# dubber.net
KiCad netlist of a schematic drawn in EAGLE
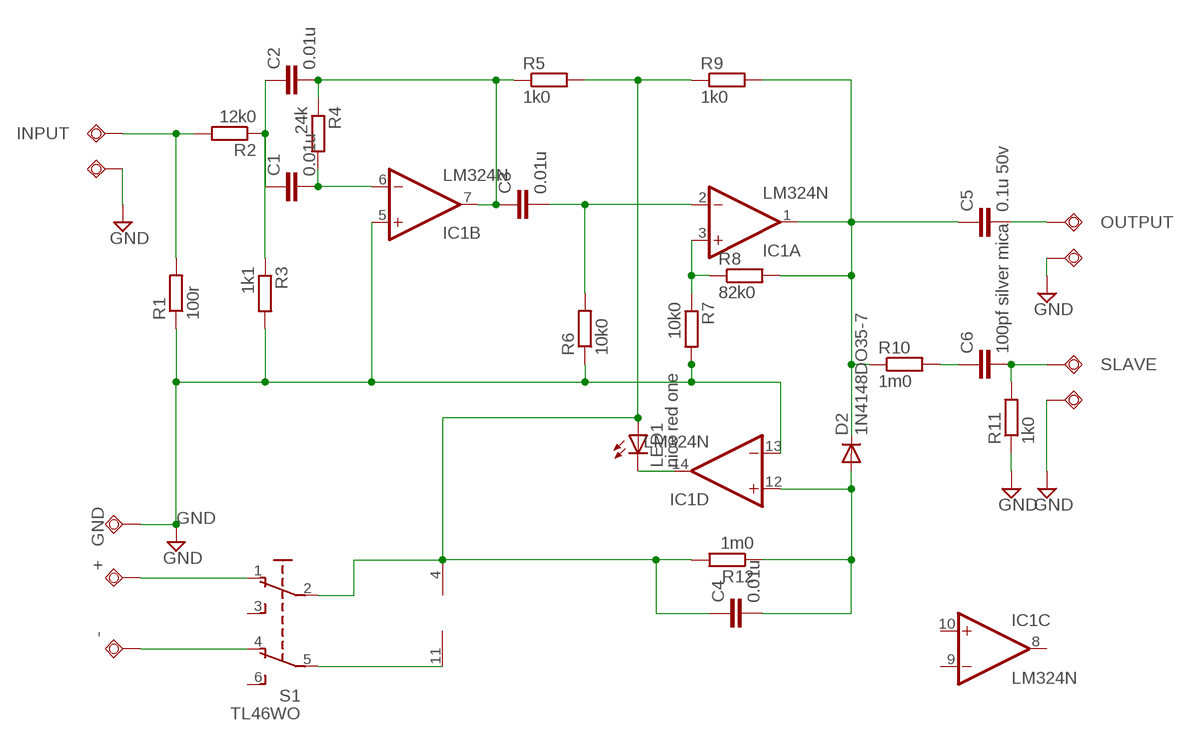
[diagram p0: schematic, sheet 1]

(export (version "E")
  (design (tool "Eeschema 10.0.6"))
  (components
    (comp (ref "+")
      (value "TPSQPAD1-13Y")
      (footprint "eagle-import:P1-13Y")
      (libsource (lib "eagle-import") (part "TPSQPAD1-13Y"))
    )
    (comp (ref "-")
      (value "TPSQPAD1-13Y")
      (footprint "eagle-import:P1-13Y")
      (libsource (lib "eagle-import") (part "TPSQPAD1-13Y"))
    )
    (comp (ref "C1")
      (value "0.01u")
      (footprint "eagle-import:C025-025X050")
      (libsource (lib "eagle-import") (part "C-EU025-025X050"))
    )
    (comp (ref "C2")
      (value "0.01u")
      (footprint "eagle-import:C025-025X050")
      (libsource (lib "eagle-import") (part "C-EU025-025X050"))
    )
    (comp (ref "C3")
      (value "0.01u")
      (footprint "eagle-import:C025-025X050")
      (libsource (lib "eagle-import") (part "C-EU025-025X050"))
    )
    (comp (ref "C4")
      (value "0.01u")
      (footprint "eagle-import:C025-025X050")
      (libsource (lib "eagle-import") (part "C-EU025-025X050"))
    )
    (comp (ref "C5")
      (value "0.1u 50v")
      (footprint "eagle-import:C025-025X050")
      (libsource (lib "eagle-import") (part "C-EU025-025X050"))
    )
    (comp (ref "C6")
      (value "100pf silver mica")
      (footprint "eagle-import:C025-025X050")
      (libsource (lib "eagle-import") (part "C-EU025-025X050"))
    )
    (comp (ref "D2")
      (value "1N4148DO35-7")
      (footprint "eagle-import:DO35-7")
      (libsource (lib "eagle-import") (part "1N4148DO35-7"))
    )
    (comp (ref "GND")
      (value "TPSQPAD1-13Y")
      (footprint "eagle-import:P1-13Y")
      (libsource (lib "eagle-import") (part "TPSQPAD1-13Y"))
    )
    (comp (ref "IC1")
      (value "LM324N")
      (footprint "eagle-import:DIL14")
      (libsource (lib "eagle-import") (part "LM324N"))
    )
    (comp (ref "INPUT")
      (value "TPSQPAD1-13Y")
      (footprint "eagle-import:P1-13Y")
      (libsource (lib "eagle-import") (part "TPSQPAD1-13Y"))
    )
    (comp (ref "LED1")
      (value "nice red one")
      (footprint "eagle-import:LED5MM")
      (libsource (lib "eagle-import") (part "LED5MM"))
    )
    (comp (ref "OUTPUT")
      (value "TPSQPAD1-13Y")
      (footprint "eagle-import:P1-13Y")
      (libsource (lib "eagle-import") (part "TPSQPAD1-13Y"))
    )
    (comp (ref "P1-G")
      (value "TPSQPAD1-13Y")
      (footprint "eagle-import:P1-13Y")
      (libsource (lib "eagle-import") (part "TPSQPAD1-13Y"))
    )
    (comp (ref "P2-G")
      (value "TPSQPAD1-13Y")
      (footprint "eagle-import:P1-13Y")
      (libsource (lib "eagle-import") (part "TPSQPAD1-13Y"))
    )
    (comp (ref "P3-G")
      (value "TPSQPAD1-13Y")
      (footprint "eagle-import:P1-13Y")
      (libsource (lib "eagle-import") (part "TPSQPAD1-13Y"))
    )
    (comp (ref "R1")
      (value "100r")
      (footprint "eagle-import:0207_10")
      (libsource (lib "eagle-import") (part "R-EU_0207/10"))
    )
    (comp (ref "R2")
      (value "12k0")
      (footprint "eagle-import:0207_10")
      (libsource (lib "eagle-import") (part "R-EU_0207/10"))
    )
    (comp (ref "R3")
      (value "1k1")
      (footprint "eagle-import:0207_10")
      (libsource (lib "eagle-import") (part "R-EU_0207/10"))
    )
    (comp (ref "R4")
      (value "24k")
      (footprint "eagle-import:0207_10")
      (libsource (lib "eagle-import") (part "R-EU_0207/10"))
    )
    (comp (ref "R5")
      (value "1k0")
      (footprint "eagle-import:0207_10")
      (libsource (lib "eagle-import") (part "R-EU_0207/10"))
    )
    (comp (ref "R6")
      (value "10k0")
      (footprint "eagle-import:0207_10")
      (libsource (lib "eagle-import") (part "R-EU_0207/10"))
    )
    (comp (ref "R7")
      (value "10k0")
      (footprint "eagle-import:0207_10")
      (libsource (lib "eagle-import") (part "R-EU_0207/10"))
    )
    (comp (ref "R8")
      (value "82k0")
      (footprint "eagle-import:0207_10")
      (libsource (lib "eagle-import") (part "R-EU_0207/10"))
    )
    (comp (ref "R9")
      (value "1k0")
      (footprint "eagle-import:0207_10")
      (libsource (lib "eagle-import") (part "R-EU_0207/10"))
    )
    (comp (ref "R10")
      (value "1m0")
      (footprint "eagle-import:0207_10")
      (libsource (lib "eagle-import") (part "R-EU_0207/10"))
    )
    (comp (ref "R11")
      (value "1k0")
      (footprint "eagle-import:0207_10")
      (libsource (lib "eagle-import") (part "R-EU_0207/10"))
    )
    (comp (ref "R12")
      (value "1m0")
      (footprint "eagle-import:0207_10")
      (libsource (lib "eagle-import") (part "R-EU_0207/10"))
    )
    (comp (ref "S1")
      (value "TL46WO")
      (footprint "eagle-import:TL4XWO")
      (libsource (lib "eagle-import") (part "TL46WO"))
    )
    (comp (ref "SLAVE")
      (value "TPSQPAD1-13Y")
      (footprint "eagle-import:P1-13Y")
      (libsource (lib "eagle-import") (part "TPSQPAD1-13Y"))
    )
  )
  (nets
    (net (code "1") (name "GND") (class "Default")
      (node (ref "GND") (pin "TP") (pinfunction "TP_TP") (pintype "input"))
      (node (ref "IC1") (pin "13") (pinfunction "-IN_13") (pintype "input"))
      (node (ref "IC1") (pin "5") (pinfunction "+IN_5") (pintype "input"))
      (node (ref "P1-G") (pin "TP") (pinfunction "TP_TP") (pintype "input"))
      (node (ref "P2-G") (pin "TP") (pinfunction "TP_TP") (pintype "input"))
      (node (ref "P3-G") (pin "TP") (pinfunction "TP_TP") (pintype "input"))
      (node (ref "R1") (pin "1") (pinfunction "1_1") (pintype "passive"))
      (node (ref "R11") (pin "1") (pinfunction "1_1") (pintype "passive"))
      (node (ref "R3") (pin "2") (pinfunction "2_2") (pintype "passive"))
      (node (ref "R6") (pin "1") (pinfunction "1_1") (pintype "passive"))
      (node (ref "R7") (pin "2") (pinfunction "2_2") (pintype "passive"))
    )
    (net (code "2") (name "Net-(C1-Pad1)") (class "Default")
      (node (ref "C1") (pin "1") (pinfunction "1_1") (pintype "passive"))
      (node (ref "C2") (pin "1") (pinfunction "1_1") (pintype "passive"))
      (node (ref "R2") (pin "1") (pinfunction "1_1") (pintype "passive"))
      (node (ref "R3") (pin "1") (pinfunction "1_1") (pintype "passive"))
    )
    (net (code "3") (name "Net-(C5-Pad2)") (class "Default")
      (node (ref "C5") (pin "2") (pinfunction "2_2") (pintype "passive"))
      (node (ref "OUTPUT") (pin "TP") (pinfunction "TP_TP") (pintype "input"))
    )
    (net (code "4") (name "Net-(C6-Pad1)") (class "Default")
      (node (ref "C6") (pin "1") (pinfunction "1_1") (pintype "passive"))
      (node (ref "R10") (pin "2") (pinfunction "2_2") (pintype "passive"))
    )
    (net (code "5") (name "Net-(C6-Pad2)") (class "Default")
      (node (ref "C6") (pin "2") (pinfunction "2_2") (pintype "passive"))
      (node (ref "R11") (pin "2") (pinfunction "2_2") (pintype "passive"))
      (node (ref "SLAVE") (pin "TP") (pinfunction "TP_TP") (pintype "input"))
    )
    (net (code "6") (name "Net-(IC1A-+IN)") (class "Default")
      (node (ref "IC1") (pin "3") (pinfunction "+IN_3") (pintype "input"))
      (node (ref "R7") (pin "1") (pinfunction "1_1") (pintype "passive"))
      (node (ref "R8") (pin "1") (pinfunction "1_1") (pintype "passive"))
    )
    (net (code "7") (name "Net-(IC1A--IN)") (class "Default")
      (node (ref "C3") (pin "2") (pinfunction "2_2") (pintype "passive"))
      (node (ref "IC1") (pin "2") (pinfunction "-IN_2") (pintype "input"))
      (node (ref "R6") (pin "2") (pinfunction "2_2") (pintype "passive"))
    )
    (net (code "8") (name "Net-(IC1A-OUT)") (class "Default")
      (node (ref "C5") (pin "1") (pinfunction "1_1") (pintype "passive"))
      (node (ref "D2") (pin "C") (pinfunction "C_C") (pintype "passive"))
      (node (ref "IC1") (pin "1") (pinfunction "OUT_1") (pintype "output"))
      (node (ref "R10") (pin "1") (pinfunction "1_1") (pintype "passive"))
      (node (ref "R8") (pin "2") (pinfunction "2_2") (pintype "passive"))
      (node (ref "R9") (pin "2") (pinfunction "2_2") (pintype "passive"))
    )
    (net (code "9") (name "Net-(IC1B--IN)") (class "Default")
      (node (ref "C1") (pin "2") (pinfunction "2_2") (pintype "passive"))
      (node (ref "IC1") (pin "6") (pinfunction "-IN_6") (pintype "input"))
      (node (ref "R4") (pin "2") (pinfunction "2_2") (pintype "passive"))
    )
    (net (code "10") (name "Net-(IC1B-OUT)") (class "Default")
      (node (ref "C2") (pin "2") (pinfunction "2_2") (pintype "passive"))
      (node (ref "C3") (pin "1") (pinfunction "1_1") (pintype "passive"))
      (node (ref "IC1") (pin "7") (pinfunction "OUT_7") (pintype "output"))
      (node (ref "R4") (pin "1") (pinfunction "1_1") (pintype "passive"))
      (node (ref "R5") (pin "1") (pinfunction "1_1") (pintype "passive"))
    )
    (net (code "11") (name "Net-(IC1D-+IN)") (class "Default")
      (node (ref "C4") (pin "2") (pinfunction "2_2") (pintype "passive"))
      (node (ref "D2") (pin "A") (pinfunction "A_A") (pintype "passive"))
      (node (ref "IC1") (pin "12") (pinfunction "+IN_12") (pintype "input"))
      (node (ref "R12") (pin "1") (pinfunction "1_1") (pintype "passive"))
    )
    (net (code "12") (name "Net-(IC1D-OUT)") (class "Default")
      (node (ref "IC1") (pin "14") (pinfunction "OUT_14") (pintype "output"))
      (node (ref "LED1") (pin "K") (pinfunction "C_K") (pintype "passive"))
    )
    (net (code "13") (name "Net-(IC1E-V+)") (class "Default")
      (node (ref "C4") (pin "1") (pinfunction "1_1") (pintype "passive"))
      (node (ref "IC1") (pin "4") (pinfunction "V+_4") (pintype "power_in"))
      (node (ref "LED1") (pin "A") (pinfunction "A_A") (pintype "passive"))
      (node (ref "R12") (pin "2") (pinfunction "2_2") (pintype "passive"))
      (node (ref "R5") (pin "2") (pinfunction "2_2") (pintype "passive"))
      (node (ref "R9") (pin "1") (pinfunction "1_1") (pintype "passive"))
      (node (ref "S1") (pin "2") (pinfunction "P_2") (pintype "passive"))
    )
    (net (code "14") (name "Net-(IC1E-V-)") (class "Default")
      (node (ref "IC1") (pin "11") (pinfunction "V-_11") (pintype "power_in"))
      (node (ref "S1") (pin "5") (pinfunction "P1_5") (pintype "passive"))
    )
    (net (code "15") (name "Net-(INPUT-PadTP)") (class "Default")
      (node (ref "INPUT") (pin "TP") (pinfunction "TP_TP") (pintype "input"))
      (node (ref "R1") (pin "2") (pinfunction "2_2") (pintype "passive"))
      (node (ref "R2") (pin "2") (pinfunction "2_2") (pintype "passive"))
    )
    (net (code "16") (name "Net-(S1-O)") (class "Default")
      (node (ref "+") (pin "TP") (pinfunction "TP_TP") (pintype "input"))
      (node (ref "S1") (pin "1") (pinfunction "O_1") (pintype "passive"))
    )
    (net (code "17") (name "Net-(S1-O1)") (class "Default")
      (node (ref "-") (pin "TP") (pinfunction "TP_TP") (pintype "input"))
      (node (ref "S1") (pin "4") (pinfunction "O1_4") (pintype "passive"))
    )
    (net (code "18") (name "unconnected-(IC1C-+IN-Pad10)") (class "Default")
      (node (ref "IC1") (pin "10") (pinfunction "+IN_10") (pintype "input"))
    )
    (net (code "19") (name "unconnected-(IC1C--IN-Pad9)") (class "Default")
      (node (ref "IC1") (pin "9") (pinfunction "-IN_9") (pintype "input"))
    )
    (net (code "20") (name "unconnected-(IC1C-OUT-Pad8)") (class "Default")
      (node (ref "IC1") (pin "8") (pinfunction "OUT_8") (pintype "output"))
    )
    (net (code "21") (name "unconnected-(S1-S-Pad3)") (class "Default")
      (node (ref "S1") (pin "3") (pinfunction "S_3") (pintype "passive"))
    )
    (net (code "22") (name "unconnected-(S1-S1-Pad6)") (class "Default")
      (node (ref "S1") (pin "6") (pinfunction "S1_6") (pintype "passive"))
    )
  )
)
